# DAC_channel.net
KiCad netlist of a schematic drawn in Altium Designer
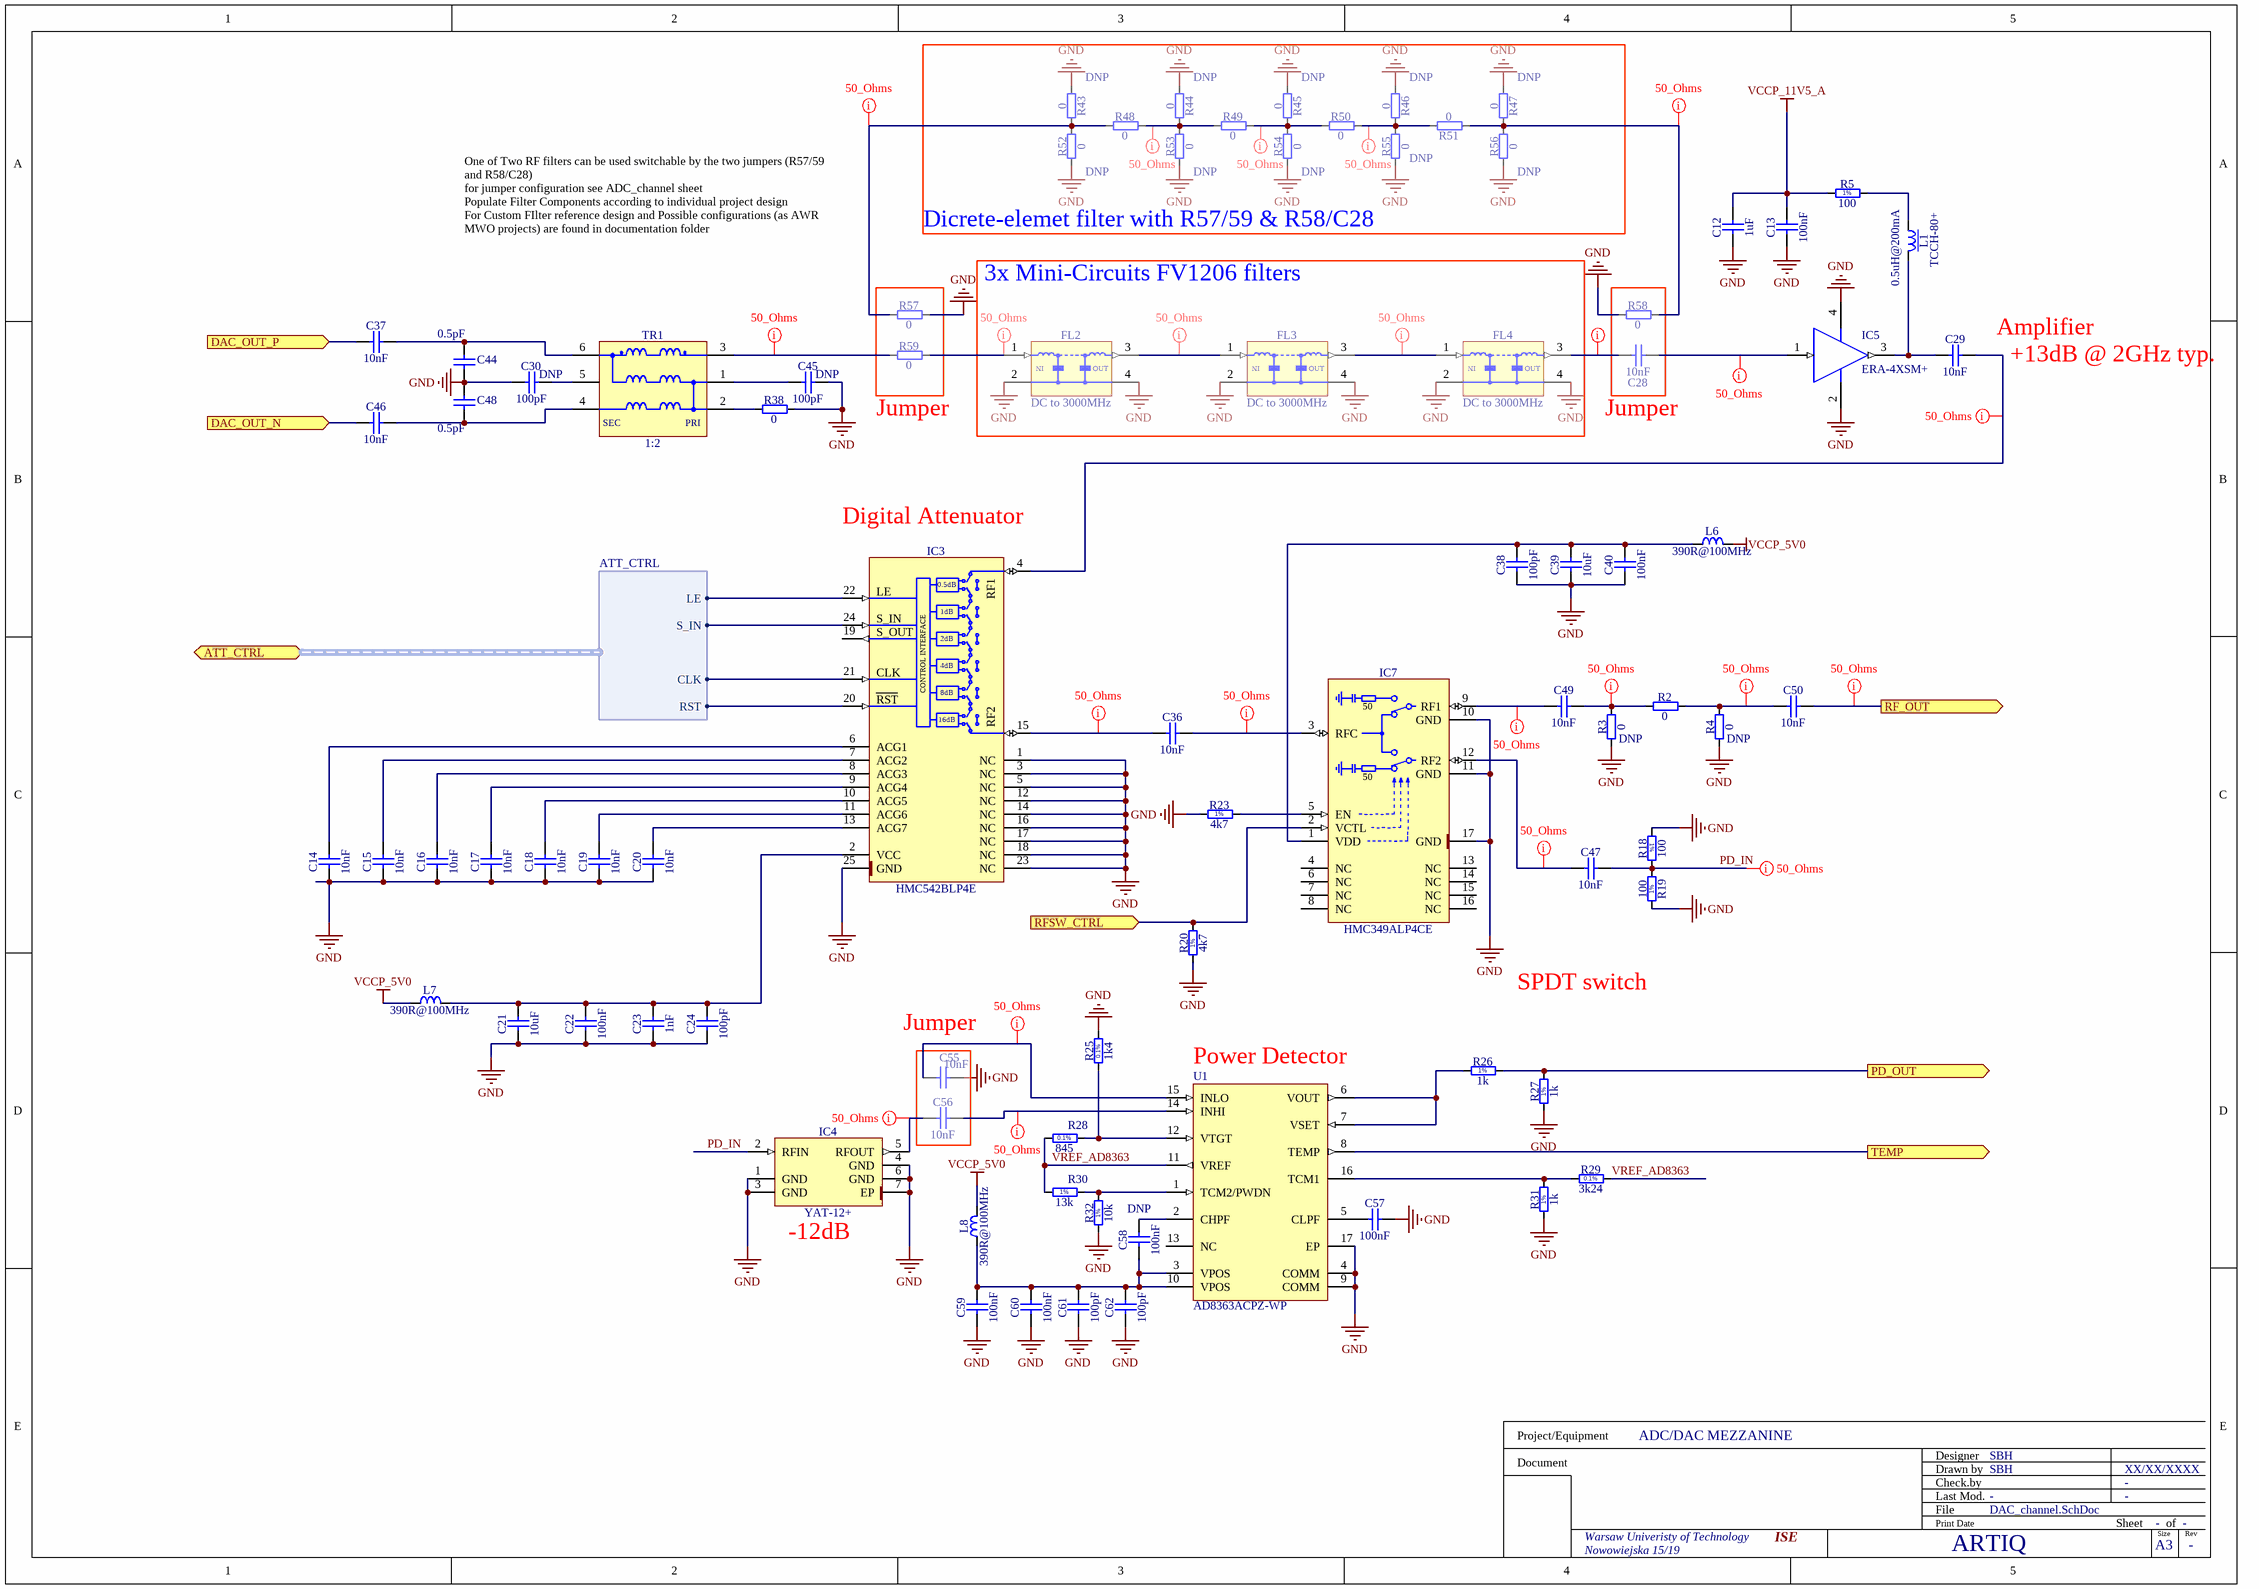
[diagram p0: DAC_channel.SchDoc]

(export (version "E")
  (design (tool "Eeschema 10.0.6"))
  (components
    (comp (ref "C12")
      (value "1uF")
      (footprint "CAPC2012X140N")
      (description "Non-polarised capacitor")
      (fields
        (field (name "PART NUMBER") "CC0805_1UF_35V_20%_X7R")
        (field (name "VOLTAGE") "35V")
        (field (name "AUTHOR") "CERN DEM JLC")
      )
      (libsource (lib "Capacitors") (part "Capacitor - non polarized"))
    )
    (comp (ref "C13")
      (value "100nF")
      (footprint "CAPC1608X87N")
      (description "Non-polarised capacitor")
      (fields
        (field (name "PART NUMBER") "CC0603_100NF_50V_10%_X7R")
        (field (name "VOLTAGE") "50V")
        (field (name "AUTHOR") "CERN DEM JLC")
      )
      (libsource (lib "Capacitors") (part "Capacitor - non polarized"))
    )
    (comp (ref "C14")
      (value "10nF")
      (footprint "CAPC1005X55N")
      (description "Non-polarised capacitor")
      (fields
        (field (name "PART NUMBER") "CC0402_10NF_16V_10%_X7R")
        (field (name "VOLTAGE") "16V")
        (field (name "AUTHOR") "CERN DEM JLC")
      )
      (libsource (lib "Capacitors") (part "Capacitor - non polarized"))
    )
    (comp (ref "C15")
      (value "10nF")
      (footprint "CAPC1005X55N")
      (description "Non-polarised capacitor")
      (fields
        (field (name "PART NUMBER") "CC0402_10NF_16V_10%_X7R")
        (field (name "VOLTAGE") "16V")
        (field (name "AUTHOR") "CERN DEM JLC")
      )
      (libsource (lib "Capacitors") (part "Capacitor - non polarized"))
    )
    (comp (ref "C16")
      (value "10nF")
      (footprint "CAPC1005X55N")
      (description "Non-polarised capacitor")
      (fields
        (field (name "PART NUMBER") "CC0402_10NF_16V_10%_X7R")
        (field (name "VOLTAGE") "16V")
        (field (name "AUTHOR") "CERN DEM JLC")
      )
      (libsource (lib "Capacitors") (part "Capacitor - non polarized"))
    )
    (comp (ref "C17")
      (value "10nF")
      (footprint "CAPC1005X55N")
      (description "Non-polarised capacitor")
      (fields
        (field (name "PART NUMBER") "CC0402_10NF_16V_10%_X7R")
        (field (name "VOLTAGE") "16V")
        (field (name "AUTHOR") "CERN DEM JLC")
      )
      (libsource (lib "Capacitors") (part "Capacitor - non polarized"))
    )
    (comp (ref "C18")
      (value "10nF")
      (footprint "CAPC1005X55N")
      (description "Non-polarised capacitor")
      (fields
        (field (name "PART NUMBER") "CC0402_10NF_16V_10%_X7R")
        (field (name "VOLTAGE") "16V")
        (field (name "AUTHOR") "CERN DEM JLC")
      )
      (libsource (lib "Capacitors") (part "Capacitor - non polarized"))
    )
    (comp (ref "C19")
      (value "10nF")
      (footprint "CAPC1005X55N")
      (description "Non-polarised capacitor")
      (fields
        (field (name "PART NUMBER") "CC0402_10NF_16V_10%_X7R")
        (field (name "VOLTAGE") "16V")
        (field (name "AUTHOR") "CERN DEM JLC")
      )
      (libsource (lib "Capacitors") (part "Capacitor - non polarized"))
    )
    (comp (ref "C20")
      (value "10nF")
      (footprint "CAPC1005X55N")
      (description "Non-polarised capacitor")
      (fields
        (field (name "PART NUMBER") "CC0402_10NF_16V_10%_X7R")
        (field (name "VOLTAGE") "16V")
        (field (name "AUTHOR") "CERN DEM JLC")
      )
      (libsource (lib "Capacitors") (part "Capacitor - non polarized"))
    )
    (comp (ref "C21")
      (value "10uF")
      (footprint "CAPC1608X80N")
      (description "Non-polarised capacitor")
      (fields
        (field (name "PART NUMBER") "CC0603_10UF_16V_20%_X5R")
        (field (name "VOLTAGE") "16V")
        (field (name "AUTHOR") "CERN DEM MR")
      )
      (libsource (lib "Capacitors") (part "Capacitor - non polarized"))
    )
    (comp (ref "C22")
      (value "100nF")
      (footprint "CAPC1005X55N")
      (description "Non-polarised capacitor")
      (fields
        (field (name "PART NUMBER") "CC0402_100NF_16V_10%_X7R")
        (field (name "VOLTAGE") "16V")
        (field (name "AUTHOR") "CERN DEM JLC")
      )
      (libsource (lib "Capacitors") (part "Capacitor - non polarized"))
    )
    (comp (ref "C23")
      (value "1nF")
      (footprint "CAPC1005X55N")
      (description "Non-polarised capacitor")
      (fields
        (field (name "PART NUMBER") "CC0402_1NF_50V_10%_X7R")
        (field (name "VOLTAGE") "50V")
        (field (name "AUTHOR") "CERN DEM JLC")
      )
      (libsource (lib "Capacitors") (part "Capacitor - non polarized"))
    )
    (comp (ref "C24")
      (value "100pF")
      (footprint "CAPC1005X55N")
      (description "Non-polarised capacitor")
      (fields
        (field (name "PART NUMBER") "CC0402_100PF_50V_5%_C0G")
        (field (name "VOLTAGE") "50V")
        (field (name "AUTHOR") "CERN DEM JLC")
      )
      (libsource (lib "Capacitors") (part "Capacitor - non polarized"))
    )
    (comp (ref "C28")
      (value "10nF")
      (footprint "CAPC1005X55N")
      (description "Non-polarised capacitor")
      (fields
        (field (name "PART NUMBER") "CC0402_10NF_16V_10%_X7R")
        (field (name "VOLTAGE") "16V")
        (field (name "AUTHOR") "CERN DEM JLC")
      )
      (libsource (lib "Capacitors") (part "Capacitor - non polarized"))
    )
    (comp (ref "C29")
      (value "10nF")
      (footprint "CAPC1005X55N")
      (description "Non-polarised capacitor")
      (fields
        (field (name "PART NUMBER") "CC0402_10NF_16V_10%_X7R")
        (field (name "VOLTAGE") "16V")
        (field (name "AUTHOR") "CERN DEM JLC")
      )
      (libsource (lib "Capacitors") (part "Capacitor - non polarized"))
    )
    (comp (ref "C30")
      (value "100pF")
      (footprint "CAPC1005X55N")
      (description "Non-polarised capacitor")
      (fields
        (field (name "PART NUMBER") "CC0402_100PF_50V_5%_C0G")
        (field (name "VOLTAGE") "50V")
        (field (name "MOUNTED") "DNP")
        (field (name "AUTHOR") "CERN DEM JLC")
      )
      (libsource (lib "Capacitors") (part "Capacitor - non polarized"))
    )
    (comp (ref "C36")
      (value "10nF")
      (footprint "CAPC1005X55N")
      (description "Non-polarised capacitor")
      (fields
        (field (name "PART NUMBER") "CC0402_10NF_16V_10%_X7R")
        (field (name "VOLTAGE") "16V")
        (field (name "AUTHOR") "CERN DEM JLC")
      )
      (libsource (lib "Capacitors") (part "Capacitor - non polarized"))
    )
    (comp (ref "C37")
      (value "10nF")
      (footprint "CAPC1005X55N")
      (description "Non-polarised capacitor")
      (fields
        (field (name "PART NUMBER") "CC0402_10NF_16V_10%_X7R")
        (field (name "VOLTAGE") "16V")
        (field (name "AUTHOR") "CERN DEM JLC")
      )
      (libsource (lib "Capacitors") (part "Capacitor - non polarized"))
    )
    (comp (ref "C38")
      (value "100pF")
      (footprint "CAPC1005X55N")
      (description "Non-polarised capacitor")
      (fields
        (field (name "PART NUMBER") "CC0402_100PF_50V_5%_C0G")
        (field (name "VOLTAGE") "50V")
        (field (name "AUTHOR") "CERN DEM JLC")
      )
      (libsource (lib "Capacitors") (part "Capacitor - non polarized"))
    )
    (comp (ref "C39")
      (value "10uF")
      (footprint "CAPC1608X80N")
      (description "Non-polarised capacitor")
      (fields
        (field (name "PART NUMBER") "CC0603_10UF_16V_20%_X5R")
        (field (name "VOLTAGE") "16V")
        (field (name "AUTHOR") "CERN DEM MR")
      )
      (libsource (lib "Capacitors") (part "Capacitor - non polarized"))
    )
    (comp (ref "C40")
      (value "100nF")
      (footprint "CAPC1005X55N")
      (description "Non-polarised capacitor")
      (fields
        (field (name "PART NUMBER") "CC0402_100NF_16V_10%_X7R")
        (field (name "VOLTAGE") "16V")
        (field (name "AUTHOR") "CERN DEM JLC")
      )
      (libsource (lib "Capacitors") (part "Capacitor - non polarized"))
    )
    (comp (ref "C44")
      (value "0.5pF")
      (footprint "CAPC0402(1005)60_M")
      (description "CAP 0.5pF 10V ±0.1pF 0402 (1005 Metric) Thickness 0.6mm SMD")
      (fields (field (name "TOLERANCE") "Â±0.1pF"))
      (libsource (lib "Altium Content Vault") (part "CMP-1034-00013-1"))
    )
    (comp (ref "C45")
      (value "100pF")
      (footprint "CAPC1005X55N")
      (description "Non-polarised capacitor")
      (fields
        (field (name "PART NUMBER") "CC0402_100PF_50V_5%_C0G")
        (field (name "VOLTAGE") "50V")
        (field (name "MOUNTED") "DNP")
        (field (name "AUTHOR") "CERN DEM JLC")
      )
      (libsource (lib "Capacitors") (part "Capacitor - non polarized"))
    )
    (comp (ref "C46")
      (value "10nF")
      (footprint "CAPC1005X55N")
      (description "Non-polarised capacitor")
      (fields
        (field (name "PART NUMBER") "CC0402_10NF_16V_10%_X7R")
        (field (name "VOLTAGE") "16V")
        (field (name "AUTHOR") "CERN DEM JLC")
      )
      (libsource (lib "Capacitors") (part "Capacitor - non polarized"))
    )
    (comp (ref "C47")
      (value "10nF")
      (footprint "CAPC1005X55N")
      (description "Non-polarised capacitor")
      (fields
        (field (name "PART NUMBER") "CC0402_10NF_16V_10%_X7R")
        (field (name "VOLTAGE") "16V")
        (field (name "AUTHOR") "CERN DEM JLC")
      )
      (libsource (lib "Capacitors") (part "Capacitor - non polarized"))
    )
    (comp (ref "C48")
      (value "0.5pF")
      (footprint "CAPC0402(1005)60_M")
      (description "CAP 0.5pF 10V ±0.1pF 0402 (1005 Metric) Thickness 0.6mm SMD")
      (fields (field (name "TOLERANCE") "Â±0.1pF"))
      (libsource (lib "Altium Content Vault") (part "CMP-1034-00013-1"))
    )
    (comp (ref "C49")
      (value "10nF")
      (footprint "CAPC1005X55N")
      (description "Non-polarised capacitor")
      (fields
        (field (name "PART NUMBER") "CC0402_10NF_16V_10%_X7R")
        (field (name "VOLTAGE") "16V")
        (field (name "AUTHOR") "CERN DEM JLC")
      )
      (libsource (lib "Capacitors") (part "Capacitor - non polarized"))
    )
    (comp (ref "C50")
      (value "10nF")
      (footprint "CAPC1005X55N")
      (description "Non-polarised capacitor")
      (fields
        (field (name "PART NUMBER") "CC0402_10NF_16V_10%_X7R")
        (field (name "VOLTAGE") "16V")
        (field (name "AUTHOR") "CERN DEM JLC")
      )
      (libsource (lib "Capacitors") (part "Capacitor - non polarized"))
    )
    (comp (ref "C55")
      (value "10nF")
      (footprint "CAPC1005X55N")
      (description "Non-polarised capacitor")
      (fields
        (field (name "PART NUMBER") "CC0402_10NF_16V_10%_X7R")
        (field (name "VOLTAGE") "16V")
        (field (name "AUTHOR") "CERN DEM JLC")
      )
      (libsource (lib "Capacitors") (part "Capacitor - non polarized"))
    )
    (comp (ref "C56")
      (value "10nF")
      (footprint "CAPC1005X55N")
      (description "Non-polarised capacitor")
      (fields
        (field (name "PART NUMBER") "CC0402_10NF_16V_10%_X7R")
        (field (name "VOLTAGE") "16V")
        (field (name "AUTHOR") "CERN DEM JLC")
      )
      (libsource (lib "Capacitors") (part "Capacitor - non polarized"))
    )
    (comp (ref "C57")
      (value "100nF")
      (footprint "CAPC1005X55N")
      (description "Non-polarised capacitor")
      (fields
        (field (name "PART NUMBER") "CC0402_100NF_16V_10%_X5R")
        (field (name "VOLTAGE") "16V")
        (field (name "AUTHOR") "CERN DEM JLC")
      )
      (libsource (lib "Capacitors") (part "Capacitor - non polarized"))
    )
    (comp (ref "C58")
      (value "100nF")
      (footprint "CAPC1005X55N")
      (description "Non-polarised capacitor")
      (fields
        (field (name "PART NUMBER") "CC0402_100NF_16V_10%_X5R")
        (field (name "VOLTAGE") "16V")
        (field (name "MOUNTED") "DNP")
        (field (name "AUTHOR") "CERN DEM JLC")
      )
      (libsource (lib "Capacitors") (part "Capacitor - non polarized"))
    )
    (comp (ref "C59")
      (value "100nF")
      (footprint "CAPC1005X55N")
      (description "Non-polarised capacitor")
      (fields
        (field (name "PART NUMBER") "CC0402_100NF_16V_10%_X5R")
        (field (name "VOLTAGE") "16V")
        (field (name "AUTHOR") "CERN DEM JLC")
      )
      (libsource (lib "Capacitors") (part "Capacitor - non polarized"))
    )
    (comp (ref "C60")
      (value "100nF")
      (footprint "CAPC1005X55N")
      (description "Non-polarised capacitor")
      (fields
        (field (name "PART NUMBER") "CC0402_100NF_16V_10%_X5R")
        (field (name "VOLTAGE") "16V")
        (field (name "AUTHOR") "CERN DEM JLC")
      )
      (libsource (lib "Capacitors") (part "Capacitor - non polarized"))
    )
    (comp (ref "C61")
      (value "100pF")
      (footprint "CAPC1005X55N")
      (description "Non-polarised capacitor")
      (fields
        (field (name "PART NUMBER") "CC0402_100PF_50V_5%_C0G")
        (field (name "VOLTAGE") "50V")
        (field (name "AUTHOR") "CERN DEM JLC")
      )
      (libsource (lib "Capacitors") (part "Capacitor - non polarized"))
    )
    (comp (ref "C62")
      (value "100pF")
      (footprint "CAPC1005X55N")
      (description "Non-polarised capacitor")
      (fields
        (field (name "PART NUMBER") "CC0402_100PF_50V_5%_C0G")
        (field (name "VOLTAGE") "50V")
        (field (name "AUTHOR") "CERN DEM JLC")
      )
      (libsource (lib "Capacitors") (part "Capacitor - non polarized"))
    )
    (comp (ref "FL2")
      (value "DC to 3000MHz")
      (footprint "FIL_MINI-CIRCUITS_FV1206")
      (description "50 Ohm DC to 3000MHz Low Pass Filter")
      (fields
        (field (name "PART NUMBER") "FIL_MINI-CIRCUITS_LFCN-3000+")
        (field (name "MANUFACTURER") "MINI-CIRCUITS")
        (field (name "AUTHOR") "CERN DEM JLC")
      )
      (libsource (lib "Inductors & Transformers") (part "FIL_MINI-CIRCUITS_LFCN-3000+"))
    )
    (comp (ref "FL3")
      (value "DC to 3000MHz")
      (footprint "FIL_MINI-CIRCUITS_FV1206")
      (description "50 Ohm DC to 3000MHz Low Pass Filter")
      (fields
        (field (name "PART NUMBER") "FIL_MINI-CIRCUITS_LFCN-3000+")
        (field (name "MANUFACTURER") "MINI-CIRCUITS")
        (field (name "AUTHOR") "CERN DEM JLC")
      )
      (libsource (lib "Inductors & Transformers") (part "FIL_MINI-CIRCUITS_LFCN-3000+"))
    )
    (comp (ref "FL4")
      (value "DC to 3000MHz")
      (footprint "FIL_MINI-CIRCUITS_FV1206")
      (description "50 Ohm DC to 3000MHz Low Pass Filter")
      (fields
        (field (name "PART NUMBER") "FIL_MINI-CIRCUITS_LFCN-3000+")
        (field (name "MANUFACTURER") "MINI-CIRCUITS")
        (field (name "AUTHOR") "CERN DEM JLC")
      )
      (libsource (lib "Inductors & Transformers") (part "FIL_MINI-CIRCUITS_LFCN-3000+"))
    )
    (comp (ref "IC3")
      (value "HMC542BLP4E")
      (footprint "QFN50P400X400X100-25N-S295")
      (description "0.5dB LSB GaAs MMIC 6-bit Digital Serial Control Attenuator, DC - 4GHz")
      (fields (field (name "MANUFACTURER") "HITTITE MICROWAVE CORP") (field (name "AUTHOR") "CERN DEM JMW"))
      (libsource (lib "ICs And Semiconductors") (part "HMC542BLP4E"))
    )
    (comp (ref "IC4")
      (value "YAT-12+")
      (footprint "MINI-CIRCUITS_MC1630")
      (description "DC to 18GHz, 2W, 50 Ohm, 4dB Attenuator")
      (fields (field (name "MANUFACTURER") "MINI-CIRCUITS") (field (name "AUTHOR") "CERN DEM JLC"))
      (libsource (lib "ICs And Semiconductors") (part "YAT-XX+"))
    )
    (comp (ref "IC5")
      (value "ERA-4XSM+")
      (footprint "MINI-CIRCUITS_WW107")
      (description "DC-4GHz Monolithic Amplifier")
      (fields (field (name "MANUFACTURER") "MINI-CIRCUITS") (field (name "AUTHOR") "CERN DEM JMW"))
      (libsource (lib "ICs And Semiconductors") (part "ERA-4XSM+"))
    )
    (comp (ref "IC7")
      (value "HMC349ALP4CE")
      (footprint "QFN65P400X400X100-17N-S255")
      (description "DC-4GHz High Isolation SPDT Non-Reflective Switch")
      (fields (field (name "MANUFACTURER") "ANALOG DEVICES") (field (name "AUTHOR") "CERN DEM JLC"))
      (libsource (lib "ICs And Semiconductors") (part "HMC349ALP4CE"))
    )
    (comp (ref "L1")
      (value "0.5uH@200mA")
      (footprint "IND_MINI-CIRCUITS_GU1604")
      (description "50 Ohms, 50 to 8200 MHz RF Choke")
      (fields
        (field (name "PART NUMBER") "IND_MINI-CIRCUITS_TCCH-80+")
        (field (name "POWER") "200mA")
        (field (name "MANUFACTURER PART NUMBER") "TCCH-80+")
        (field (name "AUTHOR") "CERN DEM JLC")
      )
      (libsource (lib "Inductors & Transformers") (part "IND_MINI-CIRCUITS_TCCH-80+"))
    )
    (comp (ref "L6")
      (value "390R@100MHz")
      (footprint "INDC1608X95N")
      (description "Inductor")
      (fields
        (field (name "PART NUMBER") "IND0603_TDK_MPZ1608R391A")
        (field (name "POWER") "1.2A")
        (field (name "AUTHOR") "CERN DEM JLC")
      )
      (libsource (lib "Inductors & Transformers") (part "Inductor"))
    )
    (comp (ref "L7")
      (value "390R@100MHz")
      (footprint "INDC1608X95N")
      (description "Inductor")
      (fields
        (field (name "PART NUMBER") "IND0603_TDK_MPZ1608R391A")
        (field (name "POWER") "1.2A")
        (field (name "AUTHOR") "CERN DEM JLC")
      )
      (libsource (lib "Inductors & Transformers") (part "Inductor"))
    )
    (comp (ref "L8")
      (value "390R@100MHz")
      (footprint "INDC1608X95N")
      (description "Inductor")
      (fields
        (field (name "PART NUMBER") "IND0603_TDK_MPZ1608R391A")
        (field (name "POWER") "1.2A")
        (field (name "AUTHOR") "CERN DEM JLC")
      )
      (libsource (lib "") (part "Inductor_1"))
    )
    (comp (ref "R2")
      (value "0")
      (footprint "RESC1005X40N")
      (description "Resistor")
      (fields
        (field (name "PART NUMBER") "R0402_0R_JUMPER")
        (field (name "MANUFACTURER") "GENERIC")
        (field (name "AUTHOR") "CERN DEM JLC")
      )
      (libsource (lib "Resistors") (part "Resistor"))
    )
    (comp (ref "R3")
      (value "0")
      (footprint "RESC1005X40N")
      (description "Resistor")
      (fields
        (field (name "PART NUMBER") "R0402_0R_JUMPER")
        (field (name "MANUFACTURER") "GENERIC")
        (field (name "MOUNTED") "DNP")
        (field (name "AUTHOR") "CERN DEM JLC")
      )
      (libsource (lib "Resistors") (part "Resistor"))
    )
    (comp (ref "R4")
      (value "0")
      (footprint "RESC1005X40N")
      (description "Resistor")
      (fields
        (field (name "PART NUMBER") "R0402_0R_JUMPER")
        (field (name "MANUFACTURER") "GENERIC")
        (field (name "MOUNTED") "DNP")
        (field (name "AUTHOR") "CERN DEM JLC")
      )
      (libsource (lib "Resistors") (part "Resistor"))
    )
    (comp (ref "R5")
      (value "100")
      (footprint "RESC3216X65N")
      (description "Resistor - 1%")
      (fields
        (field (name "PART NUMBER") "R1206_100R_1%_0.25W_100PPM")
        (field (name "POWER") "0.25W")
        (field (name "AUTHOR") "CERN DEM JLC")
      )
      (libsource (lib "Resistors") (part "Resistor - 1%"))
    )
    (comp (ref "R18")
      (value "100")
      (footprint "RESC0603X28N")
      (description "Resistor - 1%")
      (fields
        (field (name "PART NUMBER") "R0201_100R_1%_0.05W_200PPM")
        (field (name "POWER") "0.05W")
        (field (name "AUTHOR") "CERN DEM JLC")
      )
      (libsource (lib "Resistors") (part "Resistor - 1%"))
    )
    (comp (ref "R19")
      (value "100")
      (footprint "RESC0603X28N")
      (description "Resistor - 1%")
      (fields
        (field (name "PART NUMBER") "R0201_100R_1%_0.05W_200PPM")
        (field (name "POWER") "0.05W")
        (field (name "AUTHOR") "CERN DEM JLC")
      )
      (libsource (lib "Resistors") (part "Resistor - 1%"))
    )
    (comp (ref "R20")
      (value "4k7")
      (footprint "RESC1005X40N")
      (description "Resistor - 1%")
      (fields
        (field (name "PART NUMBER") "R0402_4K7_1%_0.0625W_100PPM")
        (field (name "POWER") "0.0625W")
        (field (name "AUTHOR") "CERN DEM JLC")
      )
      (libsource (lib "Resistors") (part "Resistor - 1%"))
    )
    (comp (ref "R23")
      (value "4k7")
      (footprint "RESC1005X40N")
      (description "Resistor - 1%")
      (fields
        (field (name "PART NUMBER") "R0402_4K7_1%_0.0625W_100PPM")
        (field (name "POWER") "0.0625W")
        (field (name "AUTHOR") "CERN DEM JLC")
      )
      (libsource (lib "Resistors") (part "Resistor - 1%"))
    )
    (comp (ref "R25")
      (value "1k4")
      (footprint "RESC1608X55N")
      (description "Resistor - 0.1%")
      (fields
        (field (name "PART NUMBER") "R0603_1K4_0.1%_0.063W_10PPM")
        (field (name "POWER") "0.063W")
        (field (name "AUTHOR") "CERN DEM JLC")
      )
      (libsource (lib "Resistors") (part "Resistor - 0.1%"))
    )
    (comp (ref "R26")
      (value "1k")
      (footprint "RESC1005X40N")
      (description "Resistor - 1%")
      (fields
        (field (name "PART NUMBER") "R0402_1K_1%_0.0625W_100PPM")
        (field (name "POWER") "0.0625W")
        (field (name "AUTHOR") "CERN DEM JLC")
      )
      (libsource (lib "Resistors") (part "Resistor - 1%"))
    )
    (comp (ref "R27")
      (value "1k")
      (footprint "RESC1005X40N")
      (description "Resistor - 1%")
      (fields
        (field (name "PART NUMBER") "R0402_1K_1%_0.0625W_100PPM")
        (field (name "POWER") "0.0625W")
        (field (name "AUTHOR") "CERN DEM JLC")
      )
      (libsource (lib "Resistors") (part "Resistor - 1%"))
    )
    (comp (ref "R28")
      (value "845")
      (footprint "RESC1608X55N")
      (description "Resistor - 0.1%")
      (fields
        (field (name "PART NUMBER") "R0603_845R_0.1%_0.063W_10PPM")
        (field (name "POWER") "0.063W")
        (field (name "AUTHOR") "CERN DEM JLC")
      )
      (libsource (lib "Resistors") (part "Resistor - 0.1%"))
    )
    (comp (ref "R29")
      (value "3k24")
      (footprint "RESC1608X55N")
      (description "Resistor - 0.1%")
      (fields
        (field (name "PART NUMBER") "R0603_3K24_0.1%_0.063W_10PPM")
        (field (name "POWER") "0.063W")
        (field (name "AUTHOR") "CERN DEM JLC")
      )
      (libsource (lib "Resistors") (part "Resistor - 0.1%"))
    )
    (comp (ref "R30")
      (value "13k")
      (footprint "RESC1005X40N")
      (description "Resistor - 1%")
      (fields
        (field (name "PART NUMBER") "R0402_13K_1%_0.0625W_100PPM")
        (field (name "POWER") "0.0625W")
        (field (name "AUTHOR") "CERN DEM JLC")
      )
      (libsource (lib "Resistors") (part "Resistor - 1%"))
    )
    (comp (ref "R31")
      (value "1k")
      (footprint "RESC1005X40N")
      (description "Resistor - 1%")
      (fields
        (field (name "PART NUMBER") "R0402_1K_1%_0.0625W_100PPM")
        (field (name "POWER") "0.0625W")
        (field (name "AUTHOR") "CERN DEM JLC")
      )
      (libsource (lib "Resistors") (part "Resistor - 1%"))
    )
    (comp (ref "R32")
      (value "10k")
      (footprint "RESC1005X40N")
      (description "Resistor - 1%")
      (fields
        (field (name "PART NUMBER") "R0402_10K_1%_0.0625W_100PPM")
        (field (name "POWER") "0.0625W")
        (field (name "AUTHOR") "CERN DEM JLC")
      )
      (libsource (lib "Resistors") (part "Resistor - 1%"))
    )
    (comp (ref "R38")
      (value "0")
      (footprint "RESC1005X40N")
      (description "Resistor")
      (fields
        (field (name "PART NUMBER") "R0402_0R_JUMPER")
        (field (name "MANUFACTURER") "GENERIC")
        (field (name "AUTHOR") "CERN DEM JLC")
      )
      (libsource (lib "Resistors") (part "Resistor"))
    )
    (comp (ref "R43")
      (value "0")
      (footprint "RESC1005X40N")
      (description "Resistor")
      (fields
        (field (name "PART NUMBER") "R0402_0R_JUMPER")
        (field (name "MANUFACTURER") "GENERIC")
        (field (name "MOUNTED") "DNP")
        (field (name "AUTHOR") "CERN DEM JLC")
      )
      (libsource (lib "Resistors") (part "Resistor"))
    )
    (comp (ref "R44")
      (value "0")
      (footprint "RESC1005X40N")
      (description "Resistor")
      (fields
        (field (name "PART NUMBER") "R0402_0R_JUMPER")
        (field (name "MANUFACTURER") "GENERIC")
        (field (name "MOUNTED") "DNP")
        (field (name "AUTHOR") "CERN DEM JLC")
      )
      (libsource (lib "Resistors") (part "Resistor"))
    )
    (comp (ref "R45")
      (value "0")
      (footprint "RESC1005X40N")
      (description "Resistor")
      (fields
        (field (name "PART NUMBER") "R0402_0R_JUMPER")
        (field (name "MANUFACTURER") "GENERIC")
        (field (name "MOUNTED") "DNP")
        (field (name "AUTHOR") "CERN DEM JLC")
      )
      (libsource (lib "Resistors") (part "Resistor"))
    )
    (comp (ref "R46")
      (value "0")
      (footprint "RESC1005X40N")
      (description "Resistor")
      (fields
        (field (name "PART NUMBER") "R0402_0R_JUMPER")
        (field (name "MANUFACTURER") "GENERIC")
        (field (name "MOUNTED") "DNP")
        (field (name "AUTHOR") "CERN DEM JLC")
      )
      (libsource (lib "Resistors") (part "Resistor"))
    )
    (comp (ref "R47")
      (value "0")
      (footprint "RESC1005X40N")
      (description "Resistor")
      (fields
        (field (name "PART NUMBER") "R0402_0R_JUMPER")
        (field (name "MANUFACTURER") "GENERIC")
        (field (name "MOUNTED") "DNP")
        (field (name "AUTHOR") "CERN DEM JLC")
      )
      (libsource (lib "Resistors") (part "Resistor"))
    )
    (comp (ref "R48")
      (value "0")
      (footprint "RESC1005X40N")
      (description "Resistor")
      (fields
        (field (name "PART NUMBER") "R0402_0R_JUMPER")
        (field (name "MANUFACTURER") "GENERIC")
        (field (name "AUTHOR") "CERN DEM JLC")
      )
      (libsource (lib "Resistors") (part "Resistor"))
    )
    (comp (ref "R49")
      (value "0")
      (footprint "RESC1005X40N")
      (description "Resistor")
      (fields
        (field (name "PART NUMBER") "R0402_0R_JUMPER")
        (field (name "MANUFACTURER") "GENERIC")
        (field (name "AUTHOR") "CERN DEM JLC")
      )
      (libsource (lib "Resistors") (part "Resistor"))
    )
    (comp (ref "R50")
      (value "0")
      (footprint "RESC1005X40N")
      (description "Resistor")
      (fields
        (field (name "PART NUMBER") "R0402_0R_JUMPER")
        (field (name "MANUFACTURER") "GENERIC")
        (field (name "AUTHOR") "CERN DEM JLC")
      )
      (libsource (lib "Resistors") (part "Resistor"))
    )
    (comp (ref "R51")
      (value "0")
      (footprint "RESC1005X40N")
      (description "Resistor")
      (fields
        (field (name "PART NUMBER") "R0402_0R_JUMPER")
        (field (name "MANUFACTURER") "GENERIC")
        (field (name "AUTHOR") "CERN DEM JLC")
      )
      (libsource (lib "Resistors") (part "Resistor"))
    )
    (comp (ref "R52")
      (value "0")
      (footprint "RESC1005X40N")
      (description "Resistor")
      (fields
        (field (name "PART NUMBER") "R0402_0R_JUMPER")
        (field (name "MANUFACTURER") "GENERIC")
        (field (name "MOUNTED") "DNP")
        (field (name "AUTHOR") "CERN DEM JLC")
      )
      (libsource (lib "Resistors") (part "Resistor"))
    )
    (comp (ref "R53")
      (value "0")
      (footprint "RESC1005X40N")
      (description "Resistor")
      (fields
        (field (name "PART NUMBER") "R0402_0R_JUMPER")
        (field (name "MANUFACTURER") "GENERIC")
        (field (name "MOUNTED") "DNP")
        (field (name "AUTHOR") "CERN DEM JLC")
      )
      (libsource (lib "Resistors") (part "Resistor"))
    )
    (comp (ref "R54")
      (value "0")
      (footprint "RESC1005X40N")
      (description "Resistor")
      (fields
        (field (name "PART NUMBER") "R0402_0R_JUMPER")
        (field (name "MANUFACTURER") "GENERIC")
        (field (name "MOUNTED") "DNP")
        (field (name "AUTHOR") "CERN DEM JLC")
      )
      (libsource (lib "Resistors") (part "Resistor"))
    )
    (comp (ref "R55")
      (value "0")
      (footprint "RESC1005X40N")
      (description "Resistor")
      (fields
        (field (name "PART NUMBER") "R0402_0R_JUMPER")
        (field (name "MANUFACTURER") "GENERIC")
        (field (name "MOUNTED") "DNP")
        (field (name "AUTHOR") "CERN DEM JLC")
      )
      (libsource (lib "Resistors") (part "Resistor"))
    )
    (comp (ref "R56")
      (value "0")
      (footprint "RESC1005X40N")
      (description "Resistor")
      (fields
        (field (name "PART NUMBER") "R0402_0R_JUMPER")
        (field (name "MANUFACTURER") "GENERIC")
        (field (name "MOUNTED") "DNP")
        (field (name "AUTHOR") "CERN DEM JLC")
      )
      (libsource (lib "Resistors") (part "Resistor"))
    )
    (comp (ref "R57")
      (value "0")
      (footprint "RESC1005X40N")
      (description "Resistor")
      (fields
        (field (name "PART NUMBER") "R0402_0R_JUMPER")
        (field (name "MANUFACTURER") "GENERIC")
        (field (name "AUTHOR") "CERN DEM JLC")
      )
      (libsource (lib "Resistors") (part "Resistor"))
    )
    (comp (ref "R58")
      (value "0")
      (footprint "RESC1005X40N")
      (description "Resistor")
      (fields
        (field (name "PART NUMBER") "R0402_0R_JUMPER")
        (field (name "MANUFACTURER") "GENERIC")
        (field (name "AUTHOR") "CERN DEM JLC")
      )
      (libsource (lib "Resistors") (part "Resistor"))
    )
    (comp (ref "R59")
      (value "0")
      (footprint "RESC1005X40N")
      (description "Resistor")
      (fields
        (field (name "PART NUMBER") "R0402_0R_JUMPER")
        (field (name "MANUFACTURER") "GENERIC")
        (field (name "AUTHOR") "CERN DEM JLC")
      )
      (libsource (lib "Resistors") (part "Resistor"))
    )
    (comp (ref "TR1")
      (value "1:2")
      (footprint "XFMR_MINI-CIRCUITS_DB1627")
      (description "50 OHMS 10 to 4000 MHz RF Transformer")
      (fields
        (field (name "PART NUMBER") "XFMR_MINI-CIRCUITS_TCM2-43X+")
        (field (name "POWER") "0.4W")
        (field (name "AUTHOR") "CERN DEM BC")
      )
      (libsource (lib "Inductors & Transformers") (part "XFMR_MINI-CIRCUITS_TCM2-43X"))
    )
    (comp (ref "U1")
      (value "AD8363ACPZ-WP")
      (footprint "ADI-CP-16-10_M")
      (description "50 Hz to 6 GHz,50 dB TruPwr™ Detector, 3µs Response Time, CP-16-10, Pb-Free, 64 Tray")
      (libsource (lib "Altium Content Vault") (part "ADI-AD8363-CP-16-10"))
    )
  )
  (nets
    (net (code "2") (name "/CLK") (class "Default")
      (node (ref "IC3") (pin "21") (pinfunction "SHIFT_CLOCK_21") (pintype "input"))
    )
    (net (code "3") (name "/DAC_OUT_N") (class "Default")
      (node (ref "C46") (pin "1") (pinfunction "1_1") (pintype "passive"))
    )
    (net (code "4") (name "/DAC_OUT_P") (class "Default")
      (node (ref "C37") (pin "1") (pinfunction "1_1") (pintype "passive"))
    )
    (net (code "5") (name "/LE") (class "Default")
      (node (ref "IC3") (pin "22") (pinfunction "LATCH_ENABLE_22") (pintype "input"))
    )
    (net (code "6") (name "/PD_IN") (class "Default")
      (node (ref "C47") (pin "2") (pinfunction "2_2") (pintype "passive"))
      (node (ref "IC4") (pin "2") (pinfunction "RFIN_2") (pintype "input"))
      (node (ref "R18") (pin "2") (pinfunction "2_2") (pintype "passive"))
      (node (ref "R19") (pin "2") (pinfunction "2_2") (pintype "passive"))
    )
    (net (code "7") (name "/PD_OUT") (class "Default")
      (node (ref "R26") (pin "2") (pinfunction "2_2") (pintype "passive"))
      (node (ref "R27") (pin "2") (pinfunction "2_2") (pintype "passive"))
    )
    (net (code "8") (name "/RFSW_CTRL") (class "Default")
      (node (ref "IC7") (pin "2") (pinfunction "VCTL_2") (pintype "input"))
      (node (ref "R20") (pin "2") (pinfunction "2_2") (pintype "passive"))
    )
    (net (code "9") (name "/RF_OUT") (class "Default")
      (node (ref "C50") (pin "2") (pinfunction "2_2") (pintype "passive"))
    )
    (net (code "10") (name "/RST") (class "Default")
      (node (ref "IC3") (pin "20") (pinfunction "~{RESET}_20") (pintype "input"))
    )
    (net (code "11") (name "/S_IN") (class "Default")
      (node (ref "IC3") (pin "24") (pinfunction "SERIAL_INPUT_24") (pintype "input"))
    )
    (net (code "12") (name "/TEMP") (class "Default")
      (node (ref "U1") (pin "8") (pinfunction "TEMP_8") (pintype "output"))
    )
    (net (code "13") (name "/VREF_AD8363") (class "Default")
      (node (ref "R28") (pin "1") (pinfunction "1_1") (pintype "passive"))
      (node (ref "R29") (pin "2") (pinfunction "2_2") (pintype "passive"))
      (node (ref "R30") (pin "1") (pinfunction "1_1") (pintype "passive"))
      (node (ref "U1") (pin "11") (pinfunction "VREF_11") (pintype "output"))
    )
    (net (code "15") (name "GND") (class "Default")
      (node (ref "C12") (pin "1") (pinfunction "1_1") (pintype "passive"))
      (node (ref "C13") (pin "1") (pinfunction "1_1") (pintype "passive"))
      (node (ref "C14") (pin "1") (pinfunction "1_1") (pintype "passive"))
      (node (ref "C15") (pin "1") (pinfunction "1_1") (pintype "passive"))
      (node (ref "C16") (pin "1") (pinfunction "1_1") (pintype "passive"))
      (node (ref "C17") (pin "1") (pinfunction "1_1") (pintype "passive"))
      (node (ref "C18") (pin "1") (pinfunction "1_1") (pintype "passive"))
      (node (ref "C19") (pin "1") (pinfunction "1_1") (pintype "passive"))
      (node (ref "C20") (pin "1") (pinfunction "1_1") (pintype "passive"))
      (node (ref "C21") (pin "1") (pinfunction "1_1") (pintype "passive"))
      (node (ref "C22") (pin "1") (pinfunction "1_1") (pintype "passive"))
      (node (ref "C23") (pin "1") (pinfunction "1_1") (pintype "passive"))
      (node (ref "C24") (pin "1") (pinfunction "1_1") (pintype "passive"))
      (node (ref "C30") (pin "1") (pinfunction "1_1") (pintype "passive"))
      (node (ref "C38") (pin "2") (pinfunction "2_2") (pintype "passive"))
      (node (ref "C39") (pin "1") (pinfunction "1_1") (pintype "passive"))
      (node (ref "C40") (pin "1") (pinfunction "1_1") (pintype "passive"))
      (node (ref "C44") (pin "1") (pinfunction "1_1") (pintype "passive"))
      (node (ref "C45") (pin "2") (pinfunction "2_2") (pintype "passive"))
      (node (ref "C48") (pin "2") (pinfunction "2_2") (pintype "passive"))
      (node (ref "C55") (pin "1") (pinfunction "1_1") (pintype "passive"))
      (node (ref "C57") (pin "2") (pinfunction "2_2") (pintype "passive"))
      (node (ref "C59") (pin "1") (pinfunction "1_1") (pintype "passive"))
      (node (ref "C60") (pin "1") (pinfunction "1_1") (pintype "passive"))
      (node (ref "C61") (pin "2") (pinfunction "2_2") (pintype "passive"))
      (node (ref "C62") (pin "2") (pinfunction "2_2") (pintype "passive"))
      (node (ref "FL2") (pin "2") (pinfunction "GND_2") (pintype "power_in"))
      (node (ref "FL2") (pin "4") (pinfunction "GND_4") (pintype "power_in"))
      (node (ref "FL3") (pin "2") (pinfunction "GND_2") (pintype "power_in"))
      (node (ref "FL3") (pin "4") (pinfunction "GND_4") (pintype "power_in"))
      (node (ref "FL4") (pin "2") (pinfunction "GND_2") (pintype "power_in"))
      (node (ref "FL4") (pin "4") (pinfunction "GND_4") (pintype "power_in"))
      (node (ref "IC3") (pin "1") (pinfunction "NC_1") (pintype "passive"))
      (node (ref "IC3") (pin "12") (pinfunction "NC_12") (pintype "passive"))
      (node (ref "IC3") (pin "14") (pinfunction "NC_14") (pintype "passive"))
      (node (ref "IC3") (pin "16") (pinfunction "NC_16") (pintype "passive"))
      (node (ref "IC3") (pin "17") (pinfunction "NC_17") (pintype "passive"))
      (node (ref "IC3") (pin "18") (pinfunction "NC_18") (pintype "passive"))
      (node (ref "IC3") (pin "23") (pinfunction "NC_23") (pintype "passive"))
      (node (ref "IC3") (pin "25") (pinfunction "GND_25") (pintype "power_in"))
      (node (ref "IC3") (pin "3") (pinfunction "NC_3") (pintype "passive"))
      (node (ref "IC3") (pin "5") (pinfunction "NC_5") (pintype "passive"))
      (node (ref "IC4") (pin "1") (pinfunction "GND_1") (pintype "power_in"))
      (node (ref "IC4") (pin "3") (pinfunction "GND_3") (pintype "power_in"))
      (node (ref "IC4") (pin "4") (pinfunction "GND_4") (pintype "power_in"))
      (node (ref "IC4") (pin "6") (pinfunction "GND_6") (pintype "power_in"))
      (node (ref "IC4") (pin "7") (pinfunction "EP_7") (pintype "power_in"))
      (node (ref "IC5") (pin "2") (pinfunction "GND_2") (pintype "power_in"))
      (node (ref "IC5") (pin "4") (pinfunction "GND_4") (pintype "power_in"))
      (node (ref "IC7") (pin "10") (pinfunction "GND_10") (pintype "power_in"))
      (node (ref "IC7") (pin "11") (pinfunction "GND_11") (pintype "power_in"))
      (node (ref "IC7") (pin "17") (pinfunction "GND_17") (pintype "power_in"))
      (node (ref "R18") (pin "1") (pinfunction "1_1") (pintype "passive"))
      (node (ref "R19") (pin "1") (pinfunction "1_1") (pintype "passive"))
      (node (ref "R20") (pin "1") (pinfunction "1_1") (pintype "passive"))
      (node (ref "R23") (pin "1") (pinfunction "1_1") (pintype "passive"))
      (node (ref "R25") (pin "2") (pinfunction "2_2") (pintype "passive"))
      (node (ref "R27") (pin "1") (pinfunction "1_1") (pintype "passive"))
      (node (ref "R3") (pin "1") (pinfunction "1_1") (pintype "passive"))
      (node (ref "R31") (pin "1") (pinfunction "1_1") (pintype "passive"))
      (node (ref "R32") (pin "1") (pinfunction "1_1") (pintype "passive"))
      (node (ref "R38") (pin "2") (pinfunction "2_2") (pintype "passive"))
      (node (ref "R4") (pin "1") (pinfunction "1_1") (pintype "passive"))
      (node (ref "R43") (pin "1") (pinfunction "1_1") (pintype "passive"))
      (node (ref "R44") (pin "1") (pinfunction "1_1") (pintype "passive"))
      (node (ref "R45") (pin "1") (pinfunction "1_1") (pintype "passive"))
      (node (ref "R46") (pin "1") (pinfunction "1_1") (pintype "passive"))
      (node (ref "R47") (pin "1") (pinfunction "1_1") (pintype "passive"))
      (node (ref "R52") (pin "1") (pinfunction "1_1") (pintype "passive"))
      (node (ref "R53") (pin "1") (pinfunction "1_1") (pintype "passive"))
      (node (ref "R54") (pin "1") (pinfunction "1_1") (pintype "passive"))
      (node (ref "R55") (pin "1") (pinfunction "1_1") (pintype "passive"))
      (node (ref "R56") (pin "1") (pinfunction "1_1") (pintype "passive"))
      (node (ref "R57") (pin "2") (pinfunction "2_2") (pintype "passive"))
      (node (ref "R58") (pin "2") (pinfunction "2_2") (pintype "passive"))
      (node (ref "U1") (pin "17") (pinfunction "EP_17") (pintype "power_in"))
      (node (ref "U1") (pin "4") (pinfunction "COMM_4") (pintype "power_in"))
      (node (ref "U1") (pin "9") (pinfunction "COMM_9") (pintype "power_in"))
    )
    (net (code "16") (name "Net-(C37-Pad2)") (class "Default")
      (node (ref "C37") (pin "2") (pinfunction "2_2") (pintype "passive"))
      (node (ref "C44") (pin "2") (pinfunction "2_2") (pintype "passive"))
      (node (ref "TR1") (pin "6") (pinfunction "S1_6") (pintype "passive"))
    )
    (net (code "17") (name "Net-(C45-Pad1)") (class "Default")
      (node (ref "C45") (pin "1") (pinfunction "1_1") (pintype "passive"))
      (node (ref "TR1") (pin "1") (pinfunction "P1_1") (pintype "passive"))
    )
    (net (code "18") (name "Net-(C46-Pad2)") (class "Default")
      (node (ref "C46") (pin "2") (pinfunction "2_2") (pintype "passive"))
      (node (ref "C48") (pin "1") (pinfunction "1_1") (pintype "passive"))
      (node (ref "TR1") (pin "4") (pinfunction "S1_4") (pintype "passive"))
    )
    (net (code "19") (name "Net-(C49-Pad2)") (class "Default")
      (node (ref "C49") (pin "2") (pinfunction "2_2") (pintype "passive"))
      (node (ref "R2") (pin "1") (pinfunction "1_1") (pintype "passive"))
      (node (ref "R3") (pin "2") (pinfunction "2_2") (pintype "passive"))
    )
    (net (code "20") (name "Net-(C50-Pad1)") (class "Default")
      (node (ref "C50") (pin "1") (pinfunction "1_1") (pintype "passive"))
      (node (ref "R2") (pin "2") (pinfunction "2_2") (pintype "passive"))
      (node (ref "R4") (pin "2") (pinfunction "2_2") (pintype "passive"))
    )
    (net (code "21") (name "Net-(C58-Pad1)") (class "Default")
      (node (ref "C58") (pin "1") (pinfunction "1_1") (pintype "passive"))
      (node (ref "C59") (pin "2") (pinfunction "2_2") (pintype "passive"))
      (node (ref "C60") (pin "2") (pinfunction "2_2") (pintype "passive"))
      (node (ref "C61") (pin "1") (pinfunction "1_1") (pintype "passive"))
      (node (ref "C62") (pin "1") (pinfunction "1_1") (pintype "passive"))
      (node (ref "L8") (pin "1") (pinfunction "1_1") (pintype "passive"))
      (node (ref "U1") (pin "10") (pinfunction "VPOS_10") (pintype "power_in"))
      (node (ref "U1") (pin "3") (pinfunction "VPOS_3") (pintype "power_in"))
    )
    (net (code "22") (name "Net-(FL2-RFIN)") (class "Default")
      (node (ref "FL2") (pin "1") (pinfunction "RFIN_1") (pintype "input"))
      (node (ref "R59") (pin "2") (pinfunction "2_2") (pintype "passive"))
    )
    (net (code "23") (name "Net-(FL2-RFOUT)") (class "Default")
      (node (ref "FL2") (pin "3") (pinfunction "RFOUT_3") (pintype "output"))
      (node (ref "FL3") (pin "1") (pinfunction "RFIN_1") (pintype "input"))
    )
    (net (code "24") (name "Net-(FL3-RFOUT)") (class "Default")
      (node (ref "FL3") (pin "3") (pinfunction "RFOUT_3") (pintype "output"))
      (node (ref "FL4") (pin "1") (pinfunction "RFIN_1") (pintype "input"))
    )
    (net (code "25") (name "Net-(FL4-RFOUT)") (class "Default")
      (node (ref "C28") (pin "1") (pinfunction "1_1") (pintype "passive"))
      (node (ref "FL4") (pin "3") (pinfunction "RFOUT_3") (pintype "output"))
    )
    (net (code "26") (name "Net-(IC3-ACG1)") (class "Default")
      (node (ref "C14") (pin "2") (pinfunction "2_2") (pintype "passive"))
      (node (ref "IC3") (pin "6") (pinfunction "ACG1_6") (pintype "passive"))
    )
    (net (code "27") (name "Net-(IC3-ACG2)") (class "Default")
      (node (ref "C15") (pin "2") (pinfunction "2_2") (pintype "passive"))
      (node (ref "IC3") (pin "7") (pinfunction "ACG2_7") (pintype "passive"))
    )
    (net (code "28") (name "Net-(IC3-ACG3)") (class "Default")
      (node (ref "C16") (pin "2") (pinfunction "2_2") (pintype "passive"))
      (node (ref "IC3") (pin "8") (pinfunction "ACG3_8") (pintype "passive"))
    )
    (net (code "29") (name "Net-(IC3-ACG4)") (class "Default")
      (node (ref "C17") (pin "2") (pinfunction "2_2") (pintype "passive"))
      (node (ref "IC3") (pin "9") (pinfunction "ACG4_9") (pintype "passive"))
    )
    (net (code "30") (name "Net-(IC3-ACG5)") (class "Default")
      (node (ref "C18") (pin "2") (pinfunction "2_2") (pintype "passive"))
      (node (ref "IC3") (pin "10") (pinfunction "ACG5_10") (pintype "passive"))
    )
    (net (code "31") (name "Net-(IC3-ACG6)") (class "Default")
      (node (ref "C19") (pin "2") (pinfunction "2_2") (pintype "passive"))
      (node (ref "IC3") (pin "11") (pinfunction "ACG6_11") (pintype "passive"))
    )
    (net (code "32") (name "Net-(IC3-ACG7)") (class "Default")
      (node (ref "C20") (pin "2") (pinfunction "2_2") (pintype "passive"))
      (node (ref "IC3") (pin "13") (pinfunction "ACG7_13") (pintype "passive"))
    )
    (net (code "33") (name "Net-(IC3-RF1)") (class "Default")
      (node (ref "C29") (pin "2") (pinfunction "2_2") (pintype "passive"))
      (node (ref "IC3") (pin "4") (pinfunction "RF1_4") (pintype "bidirectional"))
    )
    (net (code "34") (name "Net-(IC3-RF2)") (class "Default")
      (node (ref "C36") (pin "1") (pinfunction "1_1") (pintype "passive"))
      (node (ref "IC3") (pin "15") (pinfunction "RF2_15") (pintype "bidirectional"))
    )
    (net (code "35") (name "Net-(IC3-VCC)") (class "Default")
      (node (ref "C21") (pin "2") (pinfunction "2_2") (pintype "passive"))
      (node (ref "C22") (pin "2") (pinfunction "2_2") (pintype "passive"))
      (node (ref "C23") (pin "2") (pinfunction "2_2") (pintype "passive"))
      (node (ref "C24") (pin "2") (pinfunction "2_2") (pintype "passive"))
      (node (ref "IC3") (pin "2") (pinfunction "VCC_2") (pintype "power_in"))
      (node (ref "L7") (pin "2") (pinfunction "2_2") (pintype "passive"))
    )
    (net (code "36") (name "Net-(IC4-RFOUT)") (class "Default")
      (node (ref "C56") (pin "1") (pinfunction "1_1") (pintype "passive"))
      (node (ref "IC4") (pin "5") (pinfunction "RFOUT_5") (pintype "output"))
    )
    (net (code "37") (name "Net-(IC5-RF_IN)") (class "Default")
      (node (ref "C28") (pin "2") (pinfunction "2_2") (pintype "passive"))
      (node (ref "IC5") (pin "1") (pinfunction "RF_IN_1") (pintype "input"))
    )
    (net (code "38") (name "Net-(IC5-RF_OUT)") (class "Default")
      (node (ref "C29") (pin "1") (pinfunction "1_1") (pintype "passive"))
      (node (ref "IC5") (pin "3") (pinfunction "RF_OUT_3") (pintype "output"))
      (node (ref "L1") (pin "3") (pinfunction "3_3") (pintype "passive"))
    )
    (net (code "39") (name "Net-(IC7-EN)") (class "Default")
      (node (ref "IC7") (pin "5") (pinfunction "EN_5") (pintype "input"))
      (node (ref "R23") (pin "2") (pinfunction "2_2") (pintype "passive"))
    )
    (net (code "40") (name "Net-(IC7-RF1)") (class "Default")
      (node (ref "C49") (pin "1") (pinfunction "1_1") (pintype "passive"))
      (node (ref "IC7") (pin "9") (pinfunction "RF1_9") (pintype "bidirectional"))
    )
    (net (code "41") (name "Net-(IC7-RF2)") (class "Default")
      (node (ref "C47") (pin "1") (pinfunction "1_1") (pintype "passive"))
      (node (ref "IC7") (pin "12") (pinfunction "RF2_12") (pintype "bidirectional"))
    )
    (net (code "42") (name "Net-(IC7-RFC)") (class "Default")
      (node (ref "C36") (pin "2") (pinfunction "2_2") (pintype "passive"))
      (node (ref "IC7") (pin "3") (pinfunction "RFC_3") (pintype "bidirectional"))
    )
    (net (code "43") (name "Net-(IC7-VDD)") (class "Default")
      (node (ref "C38") (pin "1") (pinfunction "1_1") (pintype "passive"))
      (node (ref "C39") (pin "2") (pinfunction "2_2") (pintype "passive"))
      (node (ref "C40") (pin "2") (pinfunction "2_2") (pintype "passive"))
      (node (ref "IC7") (pin "1") (pinfunction "VDD_1") (pintype "power_in"))
      (node (ref "L6") (pin "1") (pinfunction "1_1") (pintype "passive"))
    )
    (net (code "44") (name "Net-(L1-Pad1)") (class "Default")
      (node (ref "L1") (pin "1") (pinfunction "1_1") (pintype "passive"))
      (node (ref "R5") (pin "2") (pinfunction "2_2") (pintype "passive"))
    )
    (net (code "45") (name "Net-(R38-Pad1)") (class "Default")
      (node (ref "R38") (pin "1") (pinfunction "1_1") (pintype "passive"))
      (node (ref "TR1") (pin "2") (pinfunction "P1_2") (pintype "passive"))
    )
    (net (code "46") (name "Net-(R43-Pad2)") (class "Default")
      (node (ref "R43") (pin "2") (pinfunction "2_2") (pintype "passive"))
      (node (ref "R48") (pin "1") (pinfunction "1_1") (pintype "passive"))
      (node (ref "R52") (pin "2") (pinfunction "2_2") (pintype "passive"))
      (node (ref "R57") (pin "1") (pinfunction "1_1") (pintype "passive"))
    )
    (net (code "47") (name "Net-(R44-Pad2)") (class "Default")
      (node (ref "R44") (pin "2") (pinfunction "2_2") (pintype "passive"))
      (node (ref "R48") (pin "2") (pinfunction "2_2") (pintype "passive"))
      (node (ref "R49") (pin "1") (pinfunction "1_1") (pintype "passive"))
      (node (ref "R53") (pin "2") (pinfunction "2_2") (pintype "passive"))
    )
    (net (code "48") (name "Net-(R45-Pad2)") (class "Default")
      (node (ref "R45") (pin "2") (pinfunction "2_2") (pintype "passive"))
      (node (ref "R49") (pin "2") (pinfunction "2_2") (pintype "passive"))
      (node (ref "R50") (pin "1") (pinfunction "1_1") (pintype "passive"))
      (node (ref "R54") (pin "2") (pinfunction "2_2") (pintype "passive"))
    )
    (net (code "49") (name "Net-(R46-Pad2)") (class "Default")
      (node (ref "R46") (pin "2") (pinfunction "2_2") (pintype "passive"))
      (node (ref "R50") (pin "2") (pinfunction "2_2") (pintype "passive"))
      (node (ref "R51") (pin "2") (pinfunction "2_2") (pintype "passive"))
      (node (ref "R55") (pin "2") (pinfunction "2_2") (pintype "passive"))
    )
    (net (code "50") (name "Net-(R47-Pad2)") (class "Default")
      (node (ref "R47") (pin "2") (pinfunction "2_2") (pintype "passive"))
      (node (ref "R51") (pin "1") (pinfunction "1_1") (pintype "passive"))
      (node (ref "R56") (pin "2") (pinfunction "2_2") (pintype "passive"))
      (node (ref "R58") (pin "1") (pinfunction "1_1") (pintype "passive"))
    )
    (net (code "51") (name "Net-(R59-Pad1)") (class "Default")
      (node (ref "R59") (pin "1") (pinfunction "1_1") (pintype "passive"))
      (node (ref "TR1") (pin "3") (pinfunction "P1_3") (pintype "passive"))
    )
    (net (code "52") (name "Net-(TR1-NC)") (class "Default")
      (node (ref "C30") (pin "2") (pinfunction "2_2") (pintype "passive"))
      (node (ref "TR1") (pin "5") (pinfunction "NC_5") (pintype "passive"))
    )
    (net (code "53") (name "Net-(U1-CHPF)") (class "Default")
      (node (ref "C58") (pin "2") (pinfunction "2_2") (pintype "passive"))
      (node (ref "U1") (pin "2") (pinfunction "CHPF_2") (pintype "passive"))
    )
    (net (code "54") (name "Net-(U1-CLPF)") (class "Default")
      (node (ref "C57") (pin "1") (pinfunction "1_1") (pintype "passive"))
      (node (ref "U1") (pin "5") (pinfunction "CLPF_5") (pintype "passive"))
    )
    (net (code "55") (name "Net-(U1-INHI)") (class "Default")
      (node (ref "C56") (pin "2") (pinfunction "2_2") (pintype "passive"))
      (node (ref "U1") (pin "14") (pinfunction "INHI_14") (pintype "input"))
    )
    (net (code "56") (name "Net-(U1-INLO)") (class "Default")
      (node (ref "C55") (pin "2") (pinfunction "2_2") (pintype "passive"))
      (node (ref "U1") (pin "15") (pinfunction "INLO_15") (pintype "input"))
    )
    (net (code "57") (name "Net-(U1-TCM1)") (class "Default")
      (node (ref "R29") (pin "1") (pinfunction "1_1") (pintype "passive"))
      (node (ref "R31") (pin "2") (pinfunction "2_2") (pintype "passive"))
      (node (ref "U1") (pin "16") (pinfunction "TCM1_16") (pintype "passive"))
    )
    (net (code "58") (name "Net-(U1-TCM2{slash}PWDN)") (class "Default")
      (node (ref "R30") (pin "2") (pinfunction "2_2") (pintype "passive"))
      (node (ref "R32") (pin "2") (pinfunction "2_2") (pintype "passive"))
      (node (ref "U1") (pin "1") (pinfunction "TCM2/PWDN_1") (pintype "input"))
    )
    (net (code "59") (name "Net-(U1-VOUT)") (class "Default")
      (node (ref "R26") (pin "1") (pinfunction "1_1") (pintype "passive"))
      (node (ref "U1") (pin "6") (pinfunction "VOUT_6") (pintype "output"))
      (node (ref "U1") (pin "7") (pinfunction "VSET_7") (pintype "input"))
    )
    (net (code "60") (name "Net-(U1-VTGT)") (class "Default")
      (node (ref "R25") (pin "1") (pinfunction "1_1") (pintype "passive"))
      (node (ref "R28") (pin "2") (pinfunction "2_2") (pintype "passive"))
      (node (ref "U1") (pin "12") (pinfunction "VTGT_12") (pintype "input"))
    )
    (net (code "61") (name "VCCP_5V0") (class "Default")
      (node (ref "L6") (pin "2") (pinfunction "2_2") (pintype "passive"))
      (node (ref "L7") (pin "1") (pinfunction "1_1") (pintype "passive"))
      (node (ref "L8") (pin "2") (pinfunction "2_2") (pintype "passive"))
    )
    (net (code "62") (name "VCCP_11V5_A") (class "Default")
      (node (ref "C12") (pin "2") (pinfunction "2_2") (pintype "passive"))
      (node (ref "C13") (pin "2") (pinfunction "2_2") (pintype "passive"))
      (node (ref "R5") (pin "1") (pinfunction "1_1") (pintype "passive"))
    )
    (net (code "63") (name "unconnected-(IC3-SERIAL_OUTPUT-Pad19)") (class "Default")
      (node (ref "IC3") (pin "19") (pinfunction "SERIAL_OUTPUT_19") (pintype "output"))
    )
    (net (code "64") (name "unconnected-(IC7-NC-Pad4)") (class "Default")
      (node (ref "IC7") (pin "4") (pinfunction "NC_4") (pintype "passive"))
    )
    (net (code "65") (name "unconnected-(IC7-NC-Pad6)") (class "Default")
      (node (ref "IC7") (pin "6") (pinfunction "NC_6") (pintype "passive"))
    )
    (net (code "66") (name "unconnected-(IC7-NC-Pad7)") (class "Default")
      (node (ref "IC7") (pin "7") (pinfunction "NC_7") (pintype "passive"))
    )
    (net (code "67") (name "unconnected-(IC7-NC-Pad8)") (class "Default")
      (node (ref "IC7") (pin "8") (pinfunction "NC_8") (pintype "passive"))
    )
    (net (code "68") (name "unconnected-(IC7-NC-Pad13)") (class "Default")
      (node (ref "IC7") (pin "13") (pinfunction "NC_13") (pintype "passive"))
    )
    (net (code "69") (name "unconnected-(IC7-NC-Pad14)") (class "Default")
      (node (ref "IC7") (pin "14") (pinfunction "NC_14") (pintype "passive"))
    )
    (net (code "70") (name "unconnected-(IC7-NC-Pad15)") (class "Default")
      (node (ref "IC7") (pin "15") (pinfunction "NC_15") (pintype "passive"))
    )
    (net (code "71") (name "unconnected-(IC7-NC-Pad16)") (class "Default")
      (node (ref "IC7") (pin "16") (pinfunction "NC_16") (pintype "passive"))
    )
    (net (code "72") (name "unconnected-(U1-NC-Pad13)") (class "Default")
      (node (ref "U1") (pin "13") (pinfunction "NC_13") (pintype "passive"))
    )
  )
)
